# adafruit-fona-800-gsm-breakoutnew.net
KiCad netlist of a schematic drawn in EAGLE
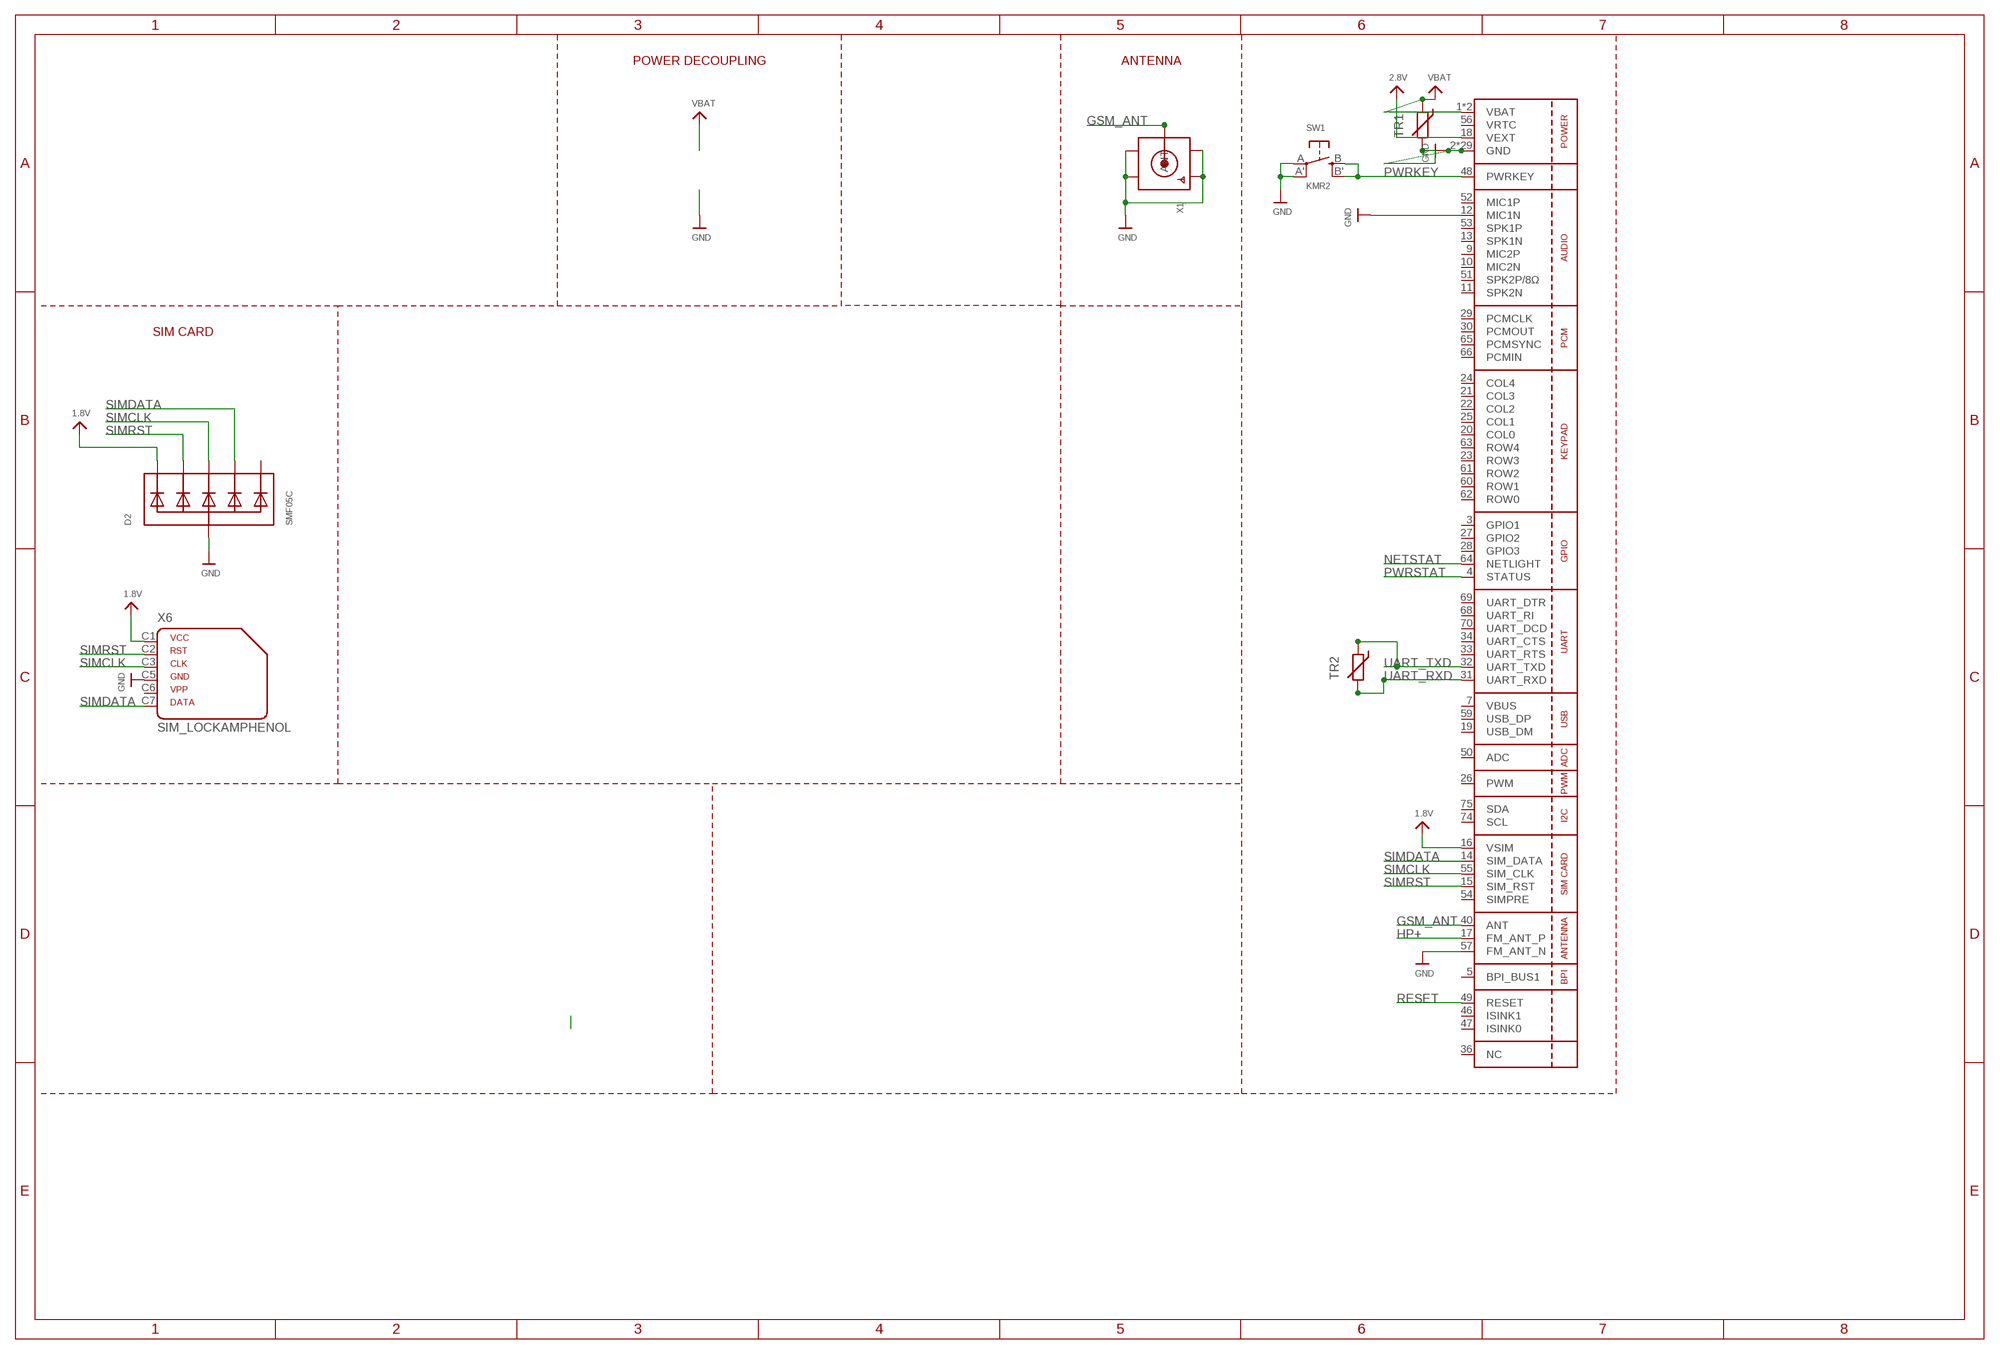
[diagram p0: schematic, sheet 1]

(export (version "E")
  (design (tool "Eeschema 10.0.6"))
  (components
    (comp (ref "D2")
      (value "SMF05C")
      (footprint "eagle-import:SOT363")
      (libsource (lib "eagle-import") (part "TVSARRAY_5LANE"))
    )
    (comp (ref "SW1")
      (value "KMR2")
      (footprint "eagle-import:BTN_KMR2_4.6X2.8")
      (libsource (lib "eagle-import") (part "SWITCH_TACT_SMT4.6X2.8"))
    )
    (comp (ref "TR1")
      (value "THERMISTOR_R-5")
      (footprint "eagle-import:R-5")
      (libsource (lib "eagle-import") (part "THERMISTOR_R-5"))
    )
    (comp (ref "TR2")
      (value "THERMISTOR_R-5")
      (footprint "eagle-import:R-5")
      (libsource (lib "eagle-import") (part "THERMISTOR_R-5"))
    )
    (comp (ref "U1")
      (value "ss")
      (footprint "eagle-import:SIM800L")
      (libsource (lib "eagle-import") (part "GSM_SIM800L"))
    )
    (comp (ref "X1")
      (value "SMACONNECTOR_EDGE_UFL")
      (footprint "eagle-import:SMA_EDGELAUNCH_UFL")
      (libsource (lib "eagle-import") (part "SMACONNECTOR_EDGE_UFL"))
    )
    (comp (ref "X6")
      (value "SIM_LOCKAMPHENOL")
      (footprint "eagle-import:C707_10M006_512_2")
      (libsource (lib "eagle-import") (part "SIM_LOCKAMPHENOL"))
    )
  )
  (nets
    (net (code "1") (name "/GSM_ANT") (class "Default")
      (node (ref "U1") (pin "40") (pinfunction "ANT_40") (pintype "bidirectional"))
      (node (ref "X1") (pin "P") (pinfunction "ANT_P") (pintype "bidirectional"))
    )
    (net (code "2") (name "/HP+") (class "Default")
      (node (ref "U1") (pin "17") (pinfunction "FM_ANT_P_17") (pintype "bidirectional"))
    )
    (net (code "3") (name "/NETSTAT") (class "Default")
      (node (ref "U1") (pin "64") (pinfunction "NETLIGHT_64") (pintype "output"))
    )
    (net (code "4") (name "/PWRKEY") (class "Default")
      (node (ref "SW1") (pin "B") (pinfunction "S_B") (pintype "passive"))
      (node (ref "SW1") (pin "B'") (pinfunction "S1_B'") (pintype "passive"))
      (node (ref "U1") (pin "48") (pinfunction "PWRKEY_48") (pintype "input"))
    )
    (net (code "5") (name "/PWRSTAT") (class "Default")
      (node (ref "U1") (pin "4") (pinfunction "STATUS_4") (pintype "output"))
    )
    (net (code "6") (name "/RESET") (class "Default")
      (node (ref "U1") (pin "49") (pinfunction "RESET_49") (pintype "input"))
    )
    (net (code "7") (name "/SIMCLK") (class "Default")
      (node (ref "D2") (pin "4") (pinfunction "C3_4") (pintype "passive"))
      (node (ref "U1") (pin "55") (pinfunction "SIM_CLK_55") (pintype "output"))
      (node (ref "X6") (pin "C3") (pinfunction "3_C3") (pintype "passive"))
    )
    (net (code "8") (name "/SIMDATA") (class "Default")
      (node (ref "D2") (pin "5") (pinfunction "C4_5") (pintype "passive"))
      (node (ref "U1") (pin "14") (pinfunction "SIM_DATA_14") (pintype "bidirectional"))
      (node (ref "X6") (pin "C7") (pinfunction "6_C7") (pintype "passive"))
    )
    (net (code "9") (name "/SIMRST") (class "Default")
      (node (ref "D2") (pin "3") (pinfunction "C2_3") (pintype "passive"))
      (node (ref "U1") (pin "15") (pinfunction "SIM_RST_15") (pintype "output"))
      (node (ref "X6") (pin "C2") (pinfunction "2_C2") (pintype "passive"))
    )
    (net (code "10") (name "/UART_RXD") (class "Default")
      (node (ref "TR2") (pin "2") (pinfunction "2_2") (pintype "passive"))
      (node (ref "U1") (pin "31") (pinfunction "UART_RXD_31") (pintype "input"))
    )
    (net (code "11") (name "/UART_TXD") (class "Default")
      (node (ref "TR2") (pin "1") (pinfunction "1_1") (pintype "passive"))
      (node (ref "U1") (pin "32") (pinfunction "UART_TXD_32") (pintype "output"))
    )
    (net (code "12") (name "/VBUS") (class "Default")
      (node (ref "U1") (pin "7") (pinfunction "VBUS_7") (pintype "power_in"))
    )
    (net (code "13") (name "/VRTC") (class "Default")
      (node (ref "U1") (pin "56") (pinfunction "VRTC_56") (pintype "power_in"))
    )
    (net (code "14") (name "1.8V") (class "Default")
      (node (ref "D2") (pin "1") (pinfunction "C1_1") (pintype "passive"))
      (node (ref "U1") (pin "16") (pinfunction "VSIM_16") (pintype "power_in"))
      (node (ref "X6") (pin "C1") (pinfunction "1_C1") (pintype "passive"))
    )
    (net (code "15") (name "2.8V") (class "Default")
      (node (ref "U1") (pin "18") (pinfunction "VEXT_18") (pintype "power_in"))
    )
    (net (code "16") (name "GND") (class "Default")
      (node (ref "D2") (pin "2") (pinfunction "A_2") (pintype "passive"))
      (node (ref "SW1") (pin "A") (pinfunction "P_A") (pintype "passive"))
      (node (ref "SW1") (pin "A'") (pinfunction "P1_A'") (pintype "passive"))
      (node (ref "TR1") (pin "2") (pinfunction "2_2") (pintype "passive"))
      (node (ref "U1") (pin "12") (pinfunction "MIC1N_12") (pintype "input"))
      (node (ref "U1") (pin "2") (pinfunction "GND_2") (pintype "power_in"))
      (node (ref "U1") (pin "35") (pinfunction "GND_35") (pintype "power_in"))
      (node (ref "U1") (pin "37") (pinfunction "GND_37") (pintype "power_in"))
      (node (ref "U1") (pin "38") (pinfunction "GND_38") (pintype "power_in"))
      (node (ref "U1") (pin "39") (pinfunction "GND_39") (pintype "power_in"))
      (node (ref "U1") (pin "41") (pinfunction "GND_41") (pintype "power_in"))
      (node (ref "U1") (pin "43") (pinfunction "GND_43") (pintype "power_in"))
      (node (ref "U1") (pin "44") (pinfunction "GND_44") (pintype "power_in"))
      (node (ref "U1") (pin "45") (pinfunction "GND_45") (pintype "power_in"))
      (node (ref "U1") (pin "57") (pinfunction "FM_ANT_N_57") (pintype "bidirectional"))
      (node (ref "U1") (pin "58") (pinfunction "GND_58") (pintype "power_in"))
      (node (ref "U1") (pin "6") (pinfunction "GND_6") (pintype "power_in"))
      (node (ref "U1") (pin "67") (pinfunction "GND_67") (pintype "power_in"))
      (node (ref "U1") (pin "71") (pinfunction "GND_71") (pintype "power_in"))
      (node (ref "U1") (pin "72") (pinfunction "GND_72") (pintype "power_in"))
      (node (ref "U1") (pin "73") (pinfunction "GND_73") (pintype "power_in"))
      (node (ref "U1") (pin "76") (pinfunction "GND_76") (pintype "power_in"))
      (node (ref "U1") (pin "77") (pinfunction "GND_77") (pintype "power_in"))
      (node (ref "U1") (pin "78") (pinfunction "GND_78") (pintype "power_in"))
      (node (ref "U1") (pin "79") (pinfunction "GND_79") (pintype "power_in"))
      (node (ref "U1") (pin "8") (pinfunction "GND_8") (pintype "power_in"))
      (node (ref "U1") (pin "80") (pinfunction "GND_80") (pintype "power_in"))
      (node (ref "U1") (pin "81") (pinfunction "GND_81") (pintype "power_in"))
      (node (ref "U1") (pin "82") (pinfunction "GND_82") (pintype "power_in"))
      (node (ref "U1") (pin "83") (pinfunction "GND_83") (pintype "power_in"))
      (node (ref "U1") (pin "84") (pinfunction "GND_84") (pintype "power_in"))
      (node (ref "U1") (pin "85") (pinfunction "GND_85") (pintype "power_in"))
      (node (ref "U1") (pin "86") (pinfunction "GND_86") (pintype "power_in"))
      (node (ref "U1") (pin "87") (pinfunction "GND_87") (pintype "power_in"))
      (node (ref "U1") (pin "88") (pinfunction "GND_88") (pintype "power_in"))
      (node (ref "X1") (pin "GND@1") (pinfunction "GND1_GND@1") (pintype "power_in"))
      (node (ref "X1") (pin "GND@2") (pinfunction "GND2_GND@2") (pintype "power_in"))
      (node (ref "X1") (pin "GND@3") (pinfunction "GND3_GND@3") (pintype "power_in"))
      (node (ref "X1") (pin "GND@4") (pinfunction "GND4_GND@4") (pintype "power_in"))
      (node (ref "X6") (pin "C5") (pinfunction "4_C5") (pintype "passive"))
    )
    (net (code "17") (name "VBAT") (class "Default")
      (node (ref "TR1") (pin "1") (pinfunction "1_1") (pintype "passive"))
      (node (ref "U1") (pin "1") (pinfunction "VBAT_1") (pintype "power_in"))
      (node (ref "U1") (pin "42") (pinfunction "VBAT_42") (pintype "power_in"))
    )
    (net (code "18") (name "unconnected-(D2-C5-Pad6)") (class "Default")
      (node (ref "D2") (pin "6") (pinfunction "C5_6") (pintype "passive"))
    )
    (net (code "19") (name "unconnected-(U1-ADC-Pad50)") (class "Default")
      (node (ref "U1") (pin "50") (pinfunction "ADC_50") (pintype "input"))
    )
    (net (code "20") (name "unconnected-(U1-BPI_BUS1-Pad5)") (class "Default")
      (node (ref "U1") (pin "5") (pinfunction "BPI_BUS1_5") (pintype "output"))
    )
    (net (code "21") (name "unconnected-(U1-COL0-Pad20)") (class "Default")
      (node (ref "U1") (pin "20") (pinfunction "COL0_20") (pintype "bidirectional"))
    )
    (net (code "22") (name "unconnected-(U1-COL1-Pad25)") (class "Default")
      (node (ref "U1") (pin "25") (pinfunction "COL1_25") (pintype "bidirectional"))
    )
    (net (code "23") (name "unconnected-(U1-COL2-Pad22)") (class "Default")
      (node (ref "U1") (pin "22") (pinfunction "COL2_22") (pintype "bidirectional"))
    )
    (net (code "24") (name "unconnected-(U1-COL3-Pad21)") (class "Default")
      (node (ref "U1") (pin "21") (pinfunction "COL3_21") (pintype "bidirectional"))
    )
    (net (code "25") (name "unconnected-(U1-COL4-Pad24)") (class "Default")
      (node (ref "U1") (pin "24") (pinfunction "COL4_24") (pintype "bidirectional"))
    )
    (net (code "26") (name "unconnected-(U1-GPIO1-Pad3)") (class "Default")
      (node (ref "U1") (pin "3") (pinfunction "GPIO1_3") (pintype "bidirectional"))
    )
    (net (code "27") (name "unconnected-(U1-GPIO2-Pad27)") (class "Default")
      (node (ref "U1") (pin "27") (pinfunction "GPIO2_27") (pintype "bidirectional"))
    )
    (net (code "28") (name "unconnected-(U1-GPIO3-Pad28)") (class "Default")
      (node (ref "U1") (pin "28") (pinfunction "GPIO3_28") (pintype "bidirectional"))
    )
    (net (code "29") (name "unconnected-(U1-ISINK0-Pad47)") (class "Default")
      (node (ref "U1") (pin "47") (pinfunction "ISINK0_47") (pintype "input"))
    )
    (net (code "30") (name "unconnected-(U1-ISINK1-Pad46)") (class "Default")
      (node (ref "U1") (pin "46") (pinfunction "ISINK1_46") (pintype "input"))
    )
    (net (code "31") (name "unconnected-(U1-MIC1P-Pad52)") (class "Default")
      (node (ref "U1") (pin "52") (pinfunction "MIC1P_52") (pintype "input"))
    )
    (net (code "32") (name "unconnected-(U1-MIC2N-Pad10)") (class "Default")
      (node (ref "U1") (pin "10") (pinfunction "MIC2N_10") (pintype "input"))
    )
    (net (code "33") (name "unconnected-(U1-MIC2P-Pad9)") (class "Default")
      (node (ref "U1") (pin "9") (pinfunction "MIC2P_9") (pintype "input"))
    )
    (net (code "34") (name "unconnected-(U1-NC-Pad36)") (class "Default")
      (node (ref "U1") (pin "36") (pinfunction "NC_36") (pintype "no_connect"))
    )
    (net (code "35") (name "unconnected-(U1-PCMCLK-Pad29)") (class "Default")
      (node (ref "U1") (pin "29") (pinfunction "PCMCLK_29") (pintype "output"))
    )
    (net (code "36") (name "unconnected-(U1-PCMIN-Pad66)") (class "Default")
      (node (ref "U1") (pin "66") (pinfunction "PCMIN_66") (pintype "input"))
    )
    (net (code "37") (name "unconnected-(U1-PCMOUT-Pad30)") (class "Default")
      (node (ref "U1") (pin "30") (pinfunction "PCMOUT_30") (pintype "output"))
    )
    (net (code "38") (name "unconnected-(U1-PCMSYNC-Pad65)") (class "Default")
      (node (ref "U1") (pin "65") (pinfunction "PCMSYNC_65") (pintype "output"))
    )
    (net (code "39") (name "unconnected-(U1-PWM-Pad26)") (class "Default")
      (node (ref "U1") (pin "26") (pinfunction "PWM_26") (pintype "output"))
    )
    (net (code "40") (name "unconnected-(U1-ROW0-Pad62)") (class "Default")
      (node (ref "U1") (pin "62") (pinfunction "ROW0_62") (pintype "bidirectional"))
    )
    (net (code "41") (name "unconnected-(U1-ROW1-Pad60)") (class "Default")
      (node (ref "U1") (pin "60") (pinfunction "ROW1_60") (pintype "bidirectional"))
    )
    (net (code "42") (name "unconnected-(U1-ROW2-Pad61)") (class "Default")
      (node (ref "U1") (pin "61") (pinfunction "ROW2_61") (pintype "bidirectional"))
    )
    (net (code "43") (name "unconnected-(U1-ROW3-Pad23)") (class "Default")
      (node (ref "U1") (pin "23") (pinfunction "ROW3_23") (pintype "bidirectional"))
    )
    (net (code "44") (name "unconnected-(U1-ROW4-Pad63)") (class "Default")
      (node (ref "U1") (pin "63") (pinfunction "ROW4_63") (pintype "bidirectional"))
    )
    (net (code "45") (name "unconnected-(U1-SCL-Pad74)") (class "Default")
      (node (ref "U1") (pin "74") (pinfunction "SCL_74") (pintype "bidirectional"))
    )
    (net (code "46") (name "unconnected-(U1-SDA-Pad75)") (class "Default")
      (node (ref "U1") (pin "75") (pinfunction "SDA_75") (pintype "bidirectional"))
    )
    (net (code "47") (name "unconnected-(U1-SIMPRE-Pad54)") (class "Default")
      (node (ref "U1") (pin "54") (pinfunction "SIMPRE_54") (pintype "input"))
    )
    (net (code "48") (name "unconnected-(U1-SPK1N-Pad13)") (class "Default")
      (node (ref "U1") (pin "13") (pinfunction "SPK1N_13") (pintype "output"))
    )
    (net (code "49") (name "unconnected-(U1-SPK1P-Pad53)") (class "Default")
      (node (ref "U1") (pin "53") (pinfunction "SPK1P_53") (pintype "output"))
    )
    (net (code "50") (name "unconnected-(U1-SPK2N-Pad11)") (class "Default")
      (node (ref "U1") (pin "11") (pinfunction "SPK2N_11") (pintype "output"))
    )
    (net (code "51") (name "unconnected-(U1-SPK2P{slash}8Ω-Pad51)") (class "Default")
      (node (ref "U1") (pin "51") (pinfunction "SPK2P/8Ω_51") (pintype "output"))
    )
    (net (code "52") (name "unconnected-(U1-UART_CTS-Pad34)") (class "Default")
      (node (ref "U1") (pin "34") (pinfunction "UART_CTS_34") (pintype "output"))
    )
    (net (code "53") (name "unconnected-(U1-UART_DCD-Pad70)") (class "Default")
      (node (ref "U1") (pin "70") (pinfunction "UART_DCD_70") (pintype "input"))
    )
    (net (code "54") (name "unconnected-(U1-UART_DTR-Pad69)") (class "Default")
      (node (ref "U1") (pin "69") (pinfunction "UART_DTR_69") (pintype "input"))
    )
    (net (code "55") (name "unconnected-(U1-UART_RI-Pad68)") (class "Default")
      (node (ref "U1") (pin "68") (pinfunction "UART_RI_68") (pintype "output"))
    )
    (net (code "56") (name "unconnected-(U1-UART_RTS-Pad33)") (class "Default")
      (node (ref "U1") (pin "33") (pinfunction "UART_RTS_33") (pintype "input"))
    )
    (net (code "57") (name "unconnected-(U1-USB_DM-Pad19)") (class "Default")
      (node (ref "U1") (pin "19") (pinfunction "USB_DM_19") (pintype "bidirectional"))
    )
    (net (code "58") (name "unconnected-(U1-USB_DP-Pad59)") (class "Default")
      (node (ref "U1") (pin "59") (pinfunction "USB_DP_59") (pintype "bidirectional"))
    )
    (net (code "59") (name "unconnected-(X6-5-PadC6)") (class "Default")
      (node (ref "X6") (pin "C6") (pinfunction "5_C6") (pintype "passive"))
    )
  )
)
